# untitled.net
KiCad netlist of a schematic drawn in EAGLE
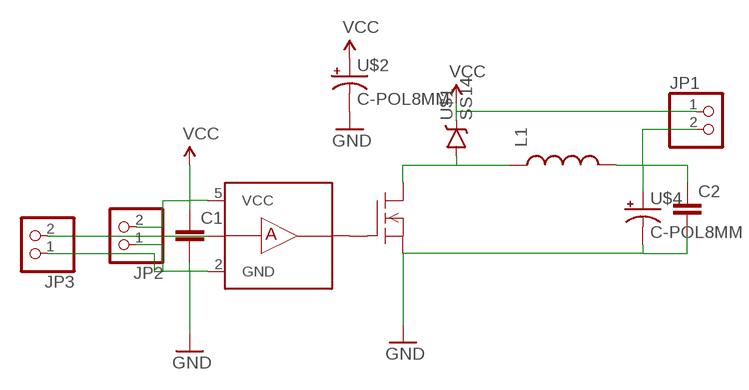
[diagram p0: schematic, sheet 1]

(export (version "E")
  (design (tool "Eeschema 10.0.6"))
  (components
    (comp (ref "C1")
      (value "CC0805")
      (footprint "eagle-import:C0805")
      (libsource (lib "eagle-import") (part "CC0805"))
    )
    (comp (ref "C2")
      (value "CC0805")
      (footprint "eagle-import:C0805")
      (libsource (lib "eagle-import") (part "CC0805"))
    )
    (comp (ref "JP1")
      (value "PINHD-1X02_2.54")
      (footprint "eagle-import:1X02")
      (libsource (lib "eagle-import") (part "PINHD-1X02_2.54"))
    )
    (comp (ref "JP2")
      (value "PINHD-1X02_2.54")
      (footprint "eagle-import:1X02")
      (libsource (lib "eagle-import") (part "PINHD-1X02_2.54"))
    )
    (comp (ref "JP3")
      (value "PINHD-1X02_2.54")
      (footprint "eagle-import:1X02")
      (libsource (lib "eagle-import") (part "PINHD-1X02_2.54"))
    )
    (comp (ref "L1")
      (value "INDUCTORDR1030")
      (footprint "eagle-import:DR1030")
      (libsource (lib "eagle-import") (part "INDUCTORDR1030"))
    )
    (comp (ref "U$1")
      (value "SS14")
      (footprint "eagle-import:SMA-DIODE")
      (libsource (lib "eagle-import") (part "SS14"))
    )
    (comp (ref "U$2")
      (value "C-POL8MM")
      (footprint "eagle-import:PCAP8")
      (libsource (lib "eagle-import") (part "C-POL8MM"))
    )
    (comp (ref "U$3")
      (value "DFET")
      (footprint "eagle-import:DIRECT-FET")
      (libsource (lib "eagle-import") (part "DFET"))
    )
    (comp (ref "U$4")
      (value "C-POL8MM")
      (footprint "eagle-import:PCAP8")
      (libsource (lib "eagle-import") (part "C-POL8MM"))
    )
    (comp (ref "U$5")
      (value "IRS44273")
      (footprint "eagle-import:SOT23-5L")
      (libsource (lib "eagle-import") (part "IRS44273"))
    )
  )
  (nets
    (net (code "1") (name "GND") (class "Default")
      (node (ref "C1") (pin "2") (pinfunction "2_2") (pintype "passive"))
      (node (ref "C2") (pin "2") (pinfunction "2_2") (pintype "passive"))
      (node (ref "JP2") (pin "1") (pinfunction "1_1") (pintype "passive"))
      (node (ref "JP3") (pin "1") (pinfunction "1_1") (pintype "passive"))
      (node (ref "U$2") (pin "P$2") (pinfunction "-_P$2") (pintype "passive"))
      (node (ref "U$3") (pin "S") (pinfunction "S_S") (pintype "bidirectional"))
      (node (ref "U$3") (pin "S1") (pinfunction "S_S1") (pintype "bidirectional"))
      (node (ref "U$4") (pin "P$2") (pinfunction "-_P$2") (pintype "passive"))
      (node (ref "U$5") (pin "2") (pinfunction "GND_2") (pintype "bidirectional"))
    )
    (net (code "2") (name "Net-(L1-Pad1)") (class "Default")
      (node (ref "L1") (pin "1") (pinfunction "1_1") (pintype "passive"))
      (node (ref "U$1") (pin "A") (pinfunction "A_A") (pintype "passive"))
      (node (ref "U$3") (pin "D") (pinfunction "D_D") (pintype "bidirectional"))
      (node (ref "U$3") (pin "D1") (pinfunction "D_D1") (pintype "bidirectional"))
    )
    (net (code "3") (name "Net-(U$3-G)") (class "Default")
      (node (ref "U$3") (pin "GATE") (pinfunction "G_GATE") (pintype "bidirectional"))
      (node (ref "U$5") (pin "3") (pinfunction "OUTA_3") (pintype "bidirectional"))
      (node (ref "U$5") (pin "4") (pinfunction "OUTA_4") (pintype "bidirectional"))
    )
    (net (code "4") (name "Net-(U$4-+)") (class "Default")
      (node (ref "C2") (pin "1") (pinfunction "1_1") (pintype "passive"))
      (node (ref "JP1") (pin "2") (pinfunction "2_2") (pintype "passive"))
      (node (ref "L1") (pin "2") (pinfunction "2_2") (pintype "passive"))
      (node (ref "U$4") (pin "P$1") (pinfunction "+_P$1") (pintype "passive"))
    )
    (net (code "5") (name "Net-(U$5-INA)") (class "Default")
      (node (ref "JP3") (pin "2") (pinfunction "2_2") (pintype "passive"))
      (node (ref "U$5") (pin "1") (pinfunction "INA_1") (pintype "bidirectional"))
    )
    (net (code "6") (name "VCC") (class "Default")
      (node (ref "C1") (pin "1") (pinfunction "1_1") (pintype "passive"))
      (node (ref "JP1") (pin "1") (pinfunction "1_1") (pintype "passive"))
      (node (ref "JP2") (pin "2") (pinfunction "2_2") (pintype "passive"))
      (node (ref "U$1") (pin "C") (pinfunction "C_C") (pintype "passive"))
      (node (ref "U$2") (pin "P$1") (pinfunction "+_P$1") (pintype "passive"))
      (node (ref "U$5") (pin "5") (pinfunction "VCC_5") (pintype "bidirectional"))
    )
  )
)
